# PCB_RTM_SATA.net
KiCad netlist of a schematic drawn in Altium Designer
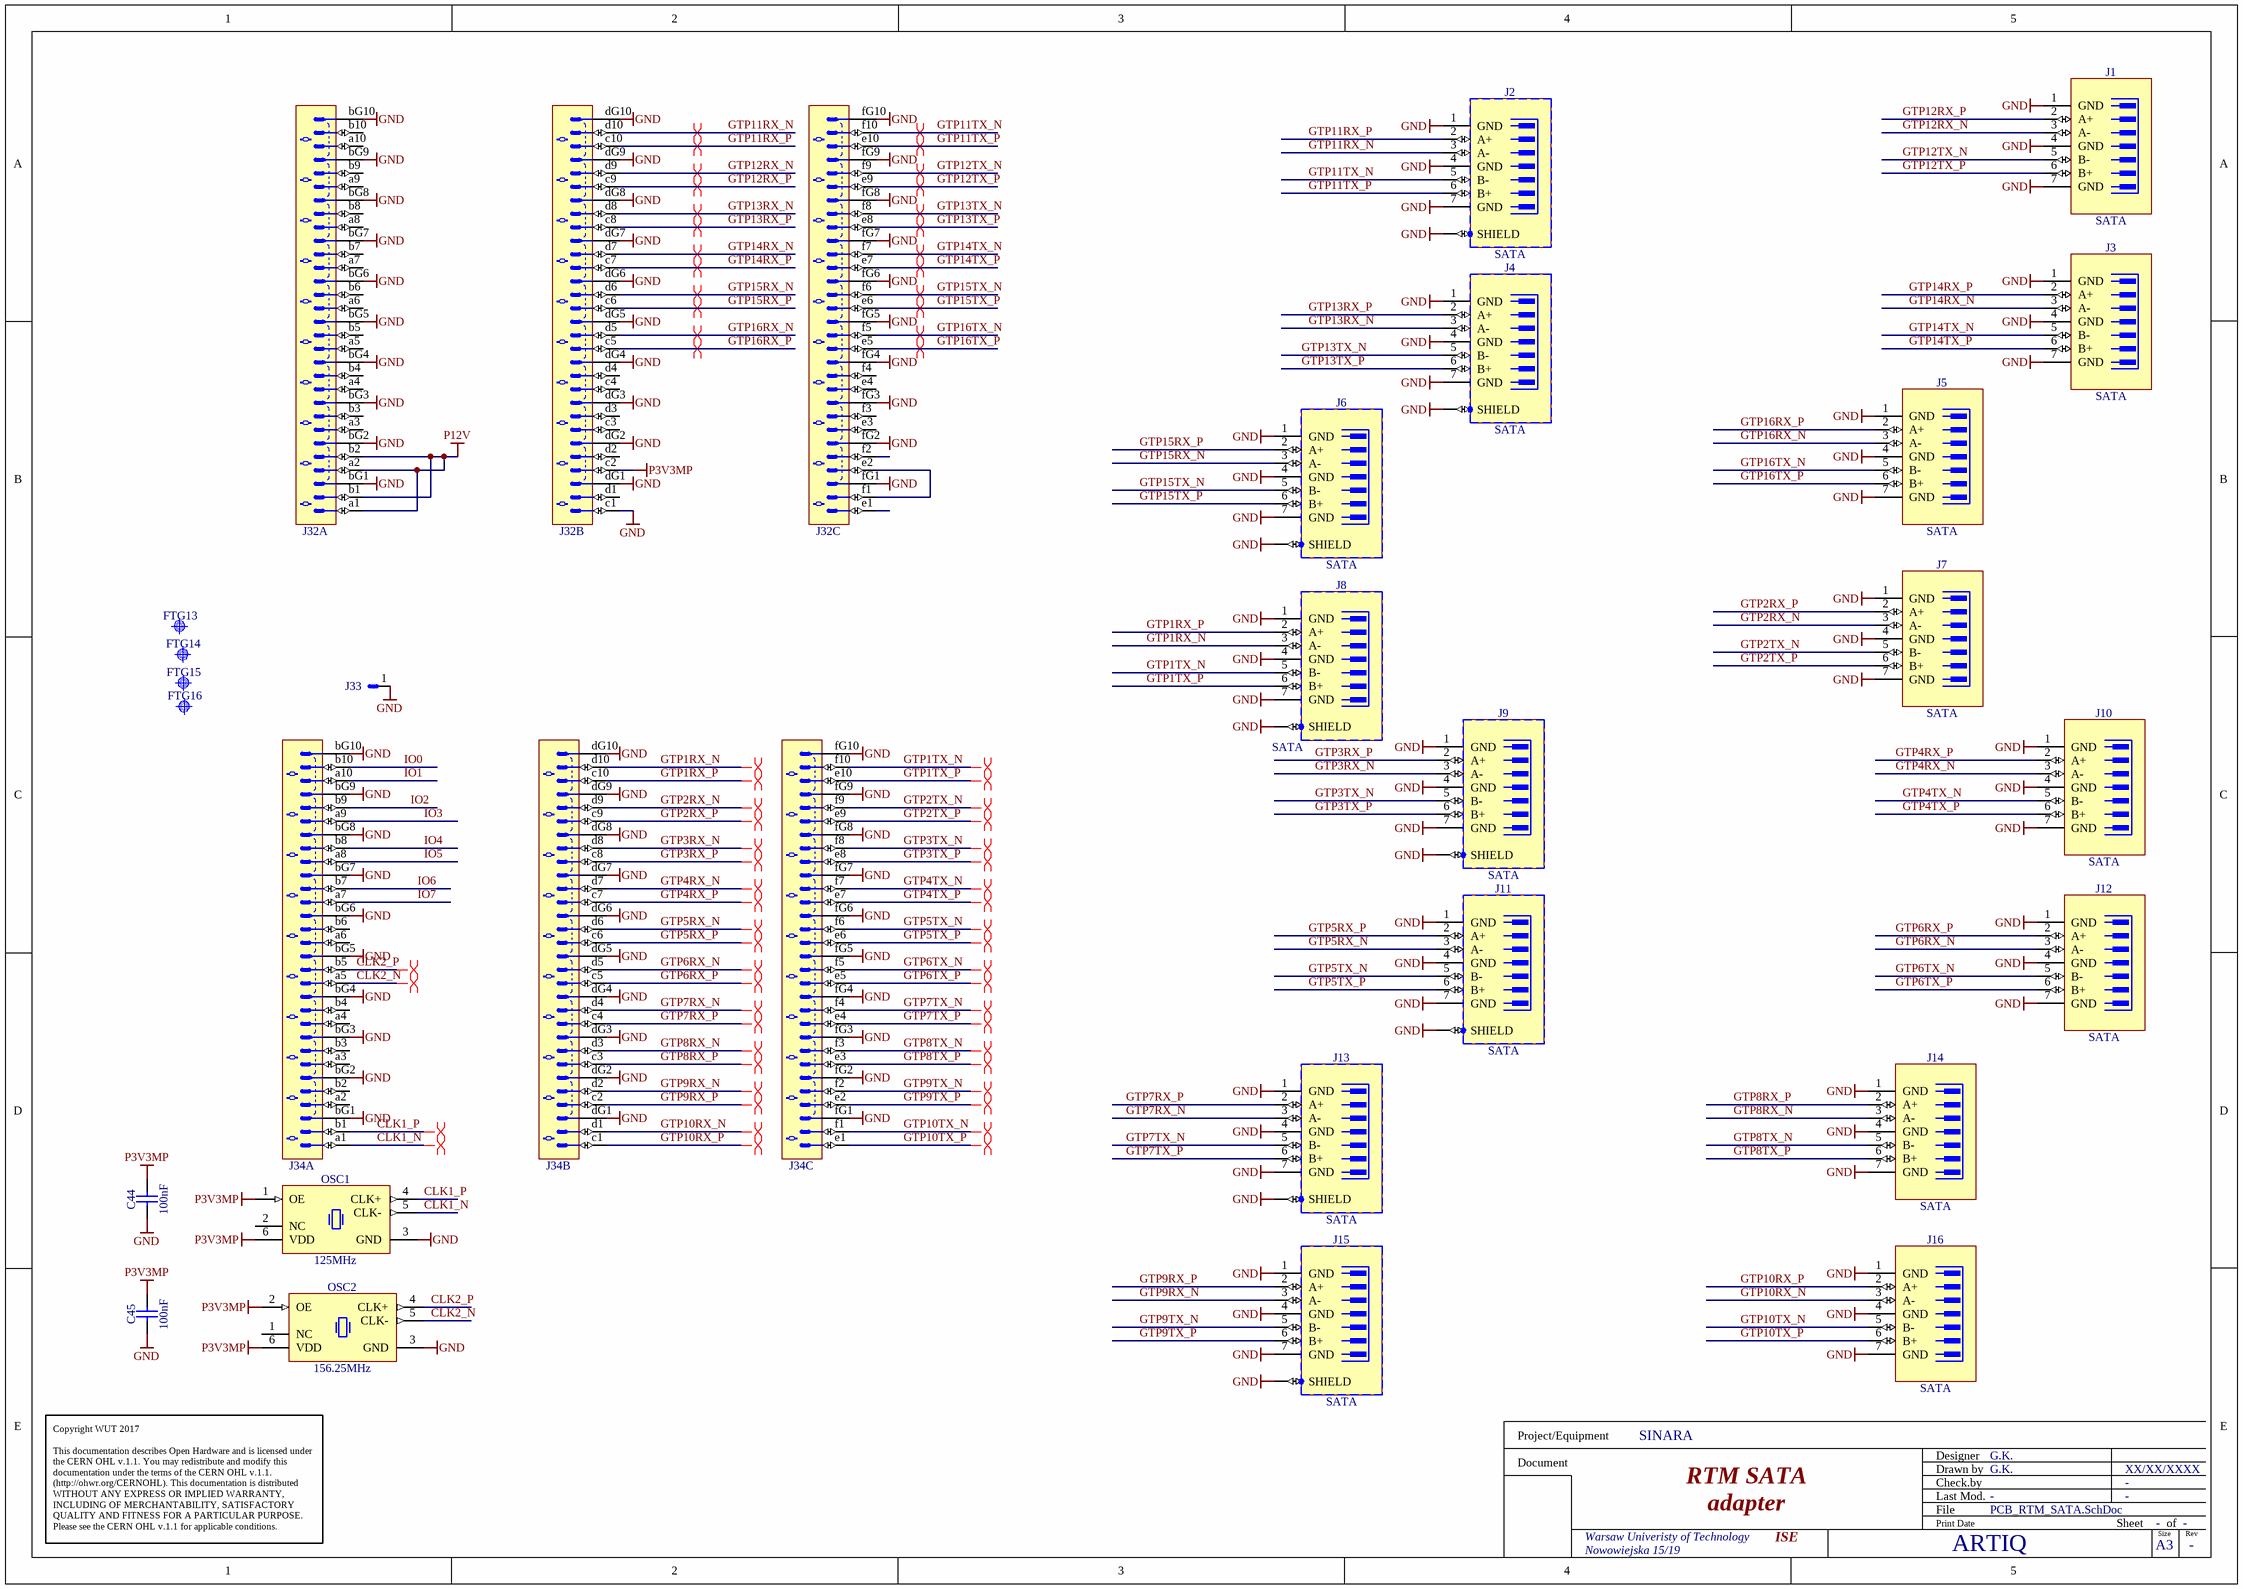
[diagram p0: PCB_RTM_SATA.SchDoc]

(export (version "E")
  (design (tool "Eeschema 10.0.6"))
  (components
    (comp (ref "C44")
      (value "100nF")
      (footprint "CAPC1005X55N")
      (description "Non-polarised capacitor")
      (fields
        (field (name "PART NUMBER") "CC0402_100NF_16V_10%_X7R")
        (field (name "VOLTAGE") "16V")
        (field (name "AUTHOR") "CERN DEM JLC")
      )
      (libsource (lib "Capacitors") (part "Capacitor - non polarized"))
    )
    (comp (ref "C45")
      (value "100nF")
      (footprint "CAPC1005X55N")
      (description "Non-polarised capacitor")
      (fields
        (field (name "PART NUMBER") "CC0402_100NF_16V_10%_X7R")
        (field (name "VOLTAGE") "16V")
        (field (name "AUTHOR") "CERN DEM JLC")
      )
      (libsource (lib "Capacitors") (part "Capacitor - non polarized"))
    )
    (comp (ref "FTG13")
      (value "Use only in PCB")
      (footprint "FIDUCIAL_TOP_C100-200")
      (description "Fiducial Target")
      (fields (field (name "PART NUMBER") "FIDUCIAL_TARGET_C100-200") (field (name "AUTHOR") "CERN DEM JLC"))
      (libsource (lib "Eletro-mechanical") (part "Fiducial Target"))
    )
    (comp (ref "FTG14")
      (value "Use only in PCB")
      (footprint "FIDUCIAL_TOP_S100-200")
      (description "Fiducial Target")
      (fields (field (name "PART NUMBER") "FIDUCIAL_TARGET_S100-200") (field (name "AUTHOR") "CERN DEM JLC"))
      (libsource (lib "Eletro-mechanical") (part "Fiducial Target"))
    )
    (comp (ref "FTG15")
      (value "Use only in PCB")
      (footprint "FIDUCIAL_TOP_S200-400")
      (description "Fiducial Target")
      (fields (field (name "PART NUMBER") "FIDUCIAL_TARGET_S200-400") (field (name "AUTHOR") "CERN DEM JLC"))
      (libsource (lib "Eletro-mechanical") (part "Fiducial Target"))
    )
    (comp (ref "FTG16")
      (value "Use only in PCB")
      (footprint "FIDUCIAL_TOP_S100-200")
      (description "Fiducial Target")
      (fields (field (name "PART NUMBER") "FIDUCIAL_TARGET_S100-200") (field (name "AUTHOR") "CERN DEM JLC"))
      (libsource (lib "Eletro-mechanical") (part "Fiducial Target"))
    )
    (comp (ref "J1")
      (value "SATA")
      (footprint "MOLEX_67800-5005")
      (description "7 Pin SATA Receptacle")
      (fields
        (field (name "PART NUMBER") "MOLEX_67800-5005")
        (field (name "MANUFACTURER") "MOLEX")
        (field (name "AUTHOR") "CERN DEM MR")
      )
      (libsource (lib "Connectors") (part "Connector SATA 7 Male"))
    )
    (comp (ref "J2")
      (value "SATA")
      (footprint "3M_5607-4200-SH")
      (description "7 Pin + 1 Shield SATA Receptacle")
      (fields
        (field (name "PART NUMBER") "3M_5607-4200-SH")
        (field (name "MANUFACTURER") "3M")
        (field (name "AUTHOR") "CERN DEM JLC")
      )
      (libsource (lib "Connectors") (part "Connector SATA 7 Male + 1 Shield"))
    )
    (comp (ref "J3")
      (value "SATA")
      (footprint "MOLEX_67800-5005")
      (description "7 Pin SATA Receptacle")
      (fields
        (field (name "PART NUMBER") "MOLEX_67800-5005")
        (field (name "MANUFACTURER") "MOLEX")
        (field (name "AUTHOR") "CERN DEM MR")
      )
      (libsource (lib "Connectors") (part "Connector SATA 7 Male"))
    )
    (comp (ref "J4")
      (value "SATA")
      (footprint "3M_5607-4200-SH")
      (description "7 Pin + 1 Shield SATA Receptacle")
      (fields
        (field (name "PART NUMBER") "3M_5607-4200-SH")
        (field (name "MANUFACTURER") "3M")
        (field (name "AUTHOR") "CERN DEM JLC")
      )
      (libsource (lib "Connectors") (part "Connector SATA 7 Male + 1 Shield"))
    )
    (comp (ref "J5")
      (value "SATA")
      (footprint "MOLEX_67800-5005")
      (description "7 Pin SATA Receptacle")
      (fields
        (field (name "PART NUMBER") "MOLEX_67800-5005")
        (field (name "MANUFACTURER") "MOLEX")
        (field (name "AUTHOR") "CERN DEM MR")
      )
      (libsource (lib "Connectors") (part "Connector SATA 7 Male"))
    )
    (comp (ref "J6")
      (value "SATA")
      (footprint "3M_5607-4200-SH")
      (description "7 Pin + 1 Shield SATA Receptacle")
      (fields
        (field (name "PART NUMBER") "3M_5607-4200-SH")
        (field (name "MANUFACTURER") "3M")
        (field (name "AUTHOR") "CERN DEM JLC")
      )
      (libsource (lib "Connectors") (part "Connector SATA 7 Male + 1 Shield"))
    )
    (comp (ref "J7")
      (value "SATA")
      (footprint "MOLEX_67800-5005")
      (description "7 Pin SATA Receptacle")
      (fields
        (field (name "PART NUMBER") "MOLEX_67800-5005")
        (field (name "MANUFACTURER") "MOLEX")
        (field (name "AUTHOR") "CERN DEM MR")
      )
      (libsource (lib "Connectors") (part "Connector SATA 7 Male"))
    )
    (comp (ref "J8")
      (value "SATA")
      (footprint "3M_5607-4200-SH")
      (description "7 Pin + 1 Shield SATA Receptacle")
      (fields
        (field (name "PART NUMBER") "3M_5607-4200-SH")
        (field (name "MANUFACTURER") "3M")
        (field (name "AUTHOR") "CERN DEM JLC")
      )
      (libsource (lib "Connectors") (part "Connector SATA 7 Male + 1 Shield"))
    )
    (comp (ref "J9")
      (value "SATA")
      (footprint "3M_5607-4200-SH")
      (description "7 Pin + 1 Shield SATA Receptacle")
      (fields
        (field (name "PART NUMBER") "3M_5607-4200-SH")
        (field (name "MANUFACTURER") "3M")
        (field (name "AUTHOR") "CERN DEM JLC")
      )
      (libsource (lib "Connectors") (part "Connector SATA 7 Male + 1 Shield"))
    )
    (comp (ref "J10")
      (value "SATA")
      (footprint "MOLEX_67800-5005")
      (description "7 Pin SATA Receptacle")
      (fields
        (field (name "PART NUMBER") "MOLEX_67800-5005")
        (field (name "MANUFACTURER") "MOLEX")
        (field (name "AUTHOR") "CERN DEM MR")
      )
      (libsource (lib "Connectors") (part "Connector SATA 7 Male"))
    )
    (comp (ref "J11")
      (value "SATA")
      (footprint "3M_5607-4200-SH")
      (description "7 Pin + 1 Shield SATA Receptacle")
      (fields
        (field (name "PART NUMBER") "3M_5607-4200-SH")
        (field (name "MANUFACTURER") "3M")
        (field (name "AUTHOR") "CERN DEM JLC")
      )
      (libsource (lib "Connectors") (part "Connector SATA 7 Male + 1 Shield"))
    )
    (comp (ref "J12")
      (value "SATA")
      (footprint "MOLEX_67800-5005")
      (description "7 Pin SATA Receptacle")
      (fields
        (field (name "PART NUMBER") "MOLEX_67800-5005")
        (field (name "MANUFACTURER") "MOLEX")
        (field (name "AUTHOR") "CERN DEM MR")
      )
      (libsource (lib "Connectors") (part "Connector SATA 7 Male"))
    )
    (comp (ref "J13")
      (value "SATA")
      (footprint "3M_5607-4200-SH")
      (description "7 Pin + 1 Shield SATA Receptacle")
      (fields
        (field (name "PART NUMBER") "3M_5607-4200-SH")
        (field (name "MANUFACTURER") "3M")
        (field (name "AUTHOR") "CERN DEM JLC")
      )
      (libsource (lib "Connectors") (part "Connector SATA 7 Male + 1 Shield"))
    )
    (comp (ref "J14")
      (value "SATA")
      (footprint "MOLEX_67800-5005")
      (description "7 Pin SATA Receptacle")
      (fields
        (field (name "PART NUMBER") "MOLEX_67800-5005")
        (field (name "MANUFACTURER") "MOLEX")
        (field (name "AUTHOR") "CERN DEM MR")
      )
      (libsource (lib "Connectors") (part "Connector SATA 7 Male"))
    )
    (comp (ref "J15")
      (value "SATA")
      (footprint "3M_5607-4200-SH")
      (description "7 Pin + 1 Shield SATA Receptacle")
      (fields
        (field (name "PART NUMBER") "3M_5607-4200-SH")
        (field (name "MANUFACTURER") "3M")
        (field (name "AUTHOR") "CERN DEM JLC")
      )
      (libsource (lib "Connectors") (part "Connector SATA 7 Male + 1 Shield"))
    )
    (comp (ref "J16")
      (value "SATA")
      (footprint "MOLEX_67800-5005")
      (description "7 Pin SATA Receptacle")
      (fields
        (field (name "PART NUMBER") "MOLEX_67800-5005")
        (field (name "MANUFACTURER") "MOLEX")
        (field (name "AUTHOR") "CERN DEM MR")
      )
      (libsource (lib "Connectors") (part "Connector SATA 7 Male"))
    )
    (comp (ref "J32")
      (value "~")
      (footprint "TYCO_6469183-1")
      (description "Connector 60 ATCA Male 30 Pairs (60 Signals) + 3x10 Ground")
      (fields (field (name "PART NUMBER") "TYCO_6469183-1"))
      (libsource (lib "Connectors") (part "Connector ATCA 60+30 Male"))
    )
    (comp (ref "J33")
      (value "~")
      (footprint "TYCO_1469265-1")
      (description "Single Pin Male")
      (fields (field (name "PART NUMBER") "TYCO_1469265-1"))
      (libsource (lib "Connectors") (part "Single Pin Male"))
    )
    (comp (ref "J34")
      (value "~")
      (footprint "TYCO_6469183-1")
      (description "Connector 60 ATCA Male 30 Pairs (60 Signals) + 3x10 Ground")
      (fields (field (name "PART NUMBER") "TYCO_6469183-1"))
      (libsource (lib "Connectors") (part "Connector ATCA 60+30 Male"))
    )
    (comp (ref "OSC1")
      (value "125MHz")
      (footprint "OSC_SILICON-LAB_SI531")
      (description "10-1400MHz, Crystal Oscillator (XO), Si531 Series")
      (fields
        (field (name "PART NUMBER") "OSC_125MHZ_SILICON-LAB_531BC125M000DG")
        (field (name "MANUFACTURER") "SILICON LABS")
        (field (name "AUTHOR") "CERN DEM MR")
      )
      (libsource (lib "ICs And Semiconductors") (part "Oscillator SILICON-LAB_Si531"))
    )
    (comp (ref "OSC2")
      (value "156.25MHz")
      (footprint "OSC_SILICON-LAB_SI530")
      (description "10-1400MHz, Crystal Oscillator (XO), Si530 Series")
      (fields
        (field (name "PART NUMBER") "OSC_156.25MHZ_SILICON-LAB_530BC156M250DG")
        (field (name "MANUFACTURER") "SILICON LABS")
        (field (name "AUTHOR") "CERN DEM MR")
      )
      (libsource (lib "ICs And Semiconductors") (part "Oscillator SILICON-LAB_Si530_a"))
    )
  )
  (nets
    (net (code "1") (name "/CLK1_N") (class "Default")
      (node (ref "J34") (pin "a1") (pinfunction "a1_a1") (pintype "bidirectional"))
      (node (ref "OSC1") (pin "5") (pinfunction "CLK-_5") (pintype "output"))
    )
    (net (code "2") (name "/CLK1_P") (class "Default")
      (node (ref "J34") (pin "b1") (pinfunction "b1_b1") (pintype "bidirectional"))
      (node (ref "OSC1") (pin "4") (pinfunction "CLK+_4") (pintype "output"))
    )
    (net (code "3") (name "/CLK2_N") (class "Default")
      (node (ref "J34") (pin "a5") (pinfunction "a5_a5") (pintype "bidirectional"))
      (node (ref "OSC2") (pin "5") (pinfunction "CLK-_5") (pintype "output"))
    )
    (net (code "4") (name "/CLK2_P") (class "Default")
      (node (ref "J34") (pin "b5") (pinfunction "b5_b5") (pintype "bidirectional"))
      (node (ref "OSC2") (pin "4") (pinfunction "CLK+_4") (pintype "output"))
    )
    (net (code "5") (name "/GTP1RX_N") (class "Default")
      (node (ref "J34") (pin "d10") (pinfunction "d10_d10") (pintype "bidirectional"))
      (node (ref "J8") (pin "3") (pinfunction "A-_3") (pintype "bidirectional"))
    )
    (net (code "6") (name "/GTP1RX_P") (class "Default")
      (node (ref "J34") (pin "c10") (pinfunction "c10_c10") (pintype "bidirectional"))
      (node (ref "J8") (pin "2") (pinfunction "A+_2") (pintype "bidirectional"))
    )
    (net (code "7") (name "/GTP1TX_N") (class "Default")
      (node (ref "J34") (pin "f10") (pinfunction "f10_f10") (pintype "bidirectional"))
      (node (ref "J8") (pin "5") (pinfunction "B-_5") (pintype "bidirectional"))
    )
    (net (code "8") (name "/GTP1TX_P") (class "Default")
      (node (ref "J34") (pin "e10") (pinfunction "e10_e10") (pintype "bidirectional"))
      (node (ref "J8") (pin "6") (pinfunction "B+_6") (pintype "bidirectional"))
    )
    (net (code "9") (name "/GTP2RX_N") (class "Default")
      (node (ref "J34") (pin "d9") (pinfunction "d9_d9") (pintype "bidirectional"))
      (node (ref "J7") (pin "3") (pinfunction "A-_3") (pintype "bidirectional"))
    )
    (net (code "10") (name "/GTP2RX_P") (class "Default")
      (node (ref "J34") (pin "c9") (pinfunction "c9_c9") (pintype "bidirectional"))
      (node (ref "J7") (pin "2") (pinfunction "A+_2") (pintype "bidirectional"))
    )
    (net (code "11") (name "/GTP2TX_N") (class "Default")
      (node (ref "J34") (pin "f9") (pinfunction "f9_f9") (pintype "bidirectional"))
      (node (ref "J7") (pin "5") (pinfunction "B-_5") (pintype "bidirectional"))
    )
    (net (code "12") (name "/GTP2TX_P") (class "Default")
      (node (ref "J34") (pin "e9") (pinfunction "e9_e9") (pintype "bidirectional"))
      (node (ref "J7") (pin "6") (pinfunction "B+_6") (pintype "bidirectional"))
    )
    (net (code "13") (name "/GTP3RX_N") (class "Default")
      (node (ref "J34") (pin "d8") (pinfunction "d8_d8") (pintype "bidirectional"))
      (node (ref "J9") (pin "3") (pinfunction "A-_3") (pintype "bidirectional"))
    )
    (net (code "14") (name "/GTP3RX_P") (class "Default")
      (node (ref "J34") (pin "c8") (pinfunction "c8_c8") (pintype "bidirectional"))
      (node (ref "J9") (pin "2") (pinfunction "A+_2") (pintype "bidirectional"))
    )
    (net (code "15") (name "/GTP3TX_N") (class "Default")
      (node (ref "J34") (pin "f8") (pinfunction "f8_f8") (pintype "bidirectional"))
      (node (ref "J9") (pin "5") (pinfunction "B-_5") (pintype "bidirectional"))
    )
    (net (code "16") (name "/GTP3TX_P") (class "Default")
      (node (ref "J34") (pin "e8") (pinfunction "e8_e8") (pintype "bidirectional"))
      (node (ref "J9") (pin "6") (pinfunction "B+_6") (pintype "bidirectional"))
    )
    (net (code "17") (name "/GTP4RX_N") (class "Default")
      (node (ref "J10") (pin "3") (pinfunction "A-_3") (pintype "bidirectional"))
      (node (ref "J34") (pin "d7") (pinfunction "d7_d7") (pintype "bidirectional"))
    )
    (net (code "18") (name "/GTP4RX_P") (class "Default")
      (node (ref "J10") (pin "2") (pinfunction "A+_2") (pintype "bidirectional"))
      (node (ref "J34") (pin "c7") (pinfunction "c7_c7") (pintype "bidirectional"))
    )
    (net (code "19") (name "/GTP4TX_N") (class "Default")
      (node (ref "J10") (pin "5") (pinfunction "B-_5") (pintype "bidirectional"))
      (node (ref "J34") (pin "f7") (pinfunction "f7_f7") (pintype "bidirectional"))
    )
    (net (code "20") (name "/GTP4TX_P") (class "Default")
      (node (ref "J10") (pin "6") (pinfunction "B+_6") (pintype "bidirectional"))
      (node (ref "J34") (pin "e7") (pinfunction "e7_e7") (pintype "bidirectional"))
    )
    (net (code "21") (name "/GTP5RX_N") (class "Default")
      (node (ref "J11") (pin "3") (pinfunction "A-_3") (pintype "bidirectional"))
      (node (ref "J34") (pin "d6") (pinfunction "d6_d6") (pintype "bidirectional"))
    )
    (net (code "22") (name "/GTP5RX_P") (class "Default")
      (node (ref "J11") (pin "2") (pinfunction "A+_2") (pintype "bidirectional"))
      (node (ref "J34") (pin "c6") (pinfunction "c6_c6") (pintype "bidirectional"))
    )
    (net (code "23") (name "/GTP5TX_N") (class "Default")
      (node (ref "J11") (pin "5") (pinfunction "B-_5") (pintype "bidirectional"))
      (node (ref "J34") (pin "f6") (pinfunction "f6_f6") (pintype "bidirectional"))
    )
    (net (code "24") (name "/GTP5TX_P") (class "Default")
      (node (ref "J11") (pin "6") (pinfunction "B+_6") (pintype "bidirectional"))
      (node (ref "J34") (pin "e6") (pinfunction "e6_e6") (pintype "bidirectional"))
    )
    (net (code "25") (name "/GTP6RX_N") (class "Default")
      (node (ref "J12") (pin "3") (pinfunction "A-_3") (pintype "bidirectional"))
      (node (ref "J34") (pin "d5") (pinfunction "d5_d5") (pintype "bidirectional"))
    )
    (net (code "26") (name "/GTP6RX_P") (class "Default")
      (node (ref "J12") (pin "2") (pinfunction "A+_2") (pintype "bidirectional"))
      (node (ref "J34") (pin "c5") (pinfunction "c5_c5") (pintype "bidirectional"))
    )
    (net (code "27") (name "/GTP6TX_N") (class "Default")
      (node (ref "J12") (pin "5") (pinfunction "B-_5") (pintype "bidirectional"))
      (node (ref "J34") (pin "f5") (pinfunction "f5_f5") (pintype "bidirectional"))
    )
    (net (code "28") (name "/GTP6TX_P") (class "Default")
      (node (ref "J12") (pin "6") (pinfunction "B+_6") (pintype "bidirectional"))
      (node (ref "J34") (pin "e5") (pinfunction "e5_e5") (pintype "bidirectional"))
    )
    (net (code "29") (name "/GTP7RX_N") (class "Default")
      (node (ref "J13") (pin "3") (pinfunction "A-_3") (pintype "bidirectional"))
      (node (ref "J34") (pin "d4") (pinfunction "d4_d4") (pintype "bidirectional"))
    )
    (net (code "30") (name "/GTP7RX_P") (class "Default")
      (node (ref "J13") (pin "2") (pinfunction "A+_2") (pintype "bidirectional"))
      (node (ref "J34") (pin "c4") (pinfunction "c4_c4") (pintype "bidirectional"))
    )
    (net (code "31") (name "/GTP7TX_N") (class "Default")
      (node (ref "J13") (pin "5") (pinfunction "B-_5") (pintype "bidirectional"))
      (node (ref "J34") (pin "f4") (pinfunction "f4_f4") (pintype "bidirectional"))
    )
    (net (code "32") (name "/GTP7TX_P") (class "Default")
      (node (ref "J13") (pin "6") (pinfunction "B+_6") (pintype "bidirectional"))
      (node (ref "J34") (pin "e4") (pinfunction "e4_e4") (pintype "bidirectional"))
    )
    (net (code "33") (name "/GTP8RX_N") (class "Default")
      (node (ref "J14") (pin "3") (pinfunction "A-_3") (pintype "bidirectional"))
      (node (ref "J34") (pin "d3") (pinfunction "d3_d3") (pintype "bidirectional"))
    )
    (net (code "34") (name "/GTP8RX_P") (class "Default")
      (node (ref "J14") (pin "2") (pinfunction "A+_2") (pintype "bidirectional"))
      (node (ref "J34") (pin "c3") (pinfunction "c3_c3") (pintype "bidirectional"))
    )
    (net (code "35") (name "/GTP8TX_N") (class "Default")
      (node (ref "J14") (pin "5") (pinfunction "B-_5") (pintype "bidirectional"))
      (node (ref "J34") (pin "f3") (pinfunction "f3_f3") (pintype "bidirectional"))
    )
    (net (code "36") (name "/GTP8TX_P") (class "Default")
      (node (ref "J14") (pin "6") (pinfunction "B+_6") (pintype "bidirectional"))
      (node (ref "J34") (pin "e3") (pinfunction "e3_e3") (pintype "bidirectional"))
    )
    (net (code "37") (name "/GTP9RX_N") (class "Default")
      (node (ref "J15") (pin "3") (pinfunction "A-_3") (pintype "bidirectional"))
      (node (ref "J34") (pin "d2") (pinfunction "d2_d2") (pintype "bidirectional"))
    )
    (net (code "38") (name "/GTP9RX_P") (class "Default")
      (node (ref "J15") (pin "2") (pinfunction "A+_2") (pintype "bidirectional"))
      (node (ref "J34") (pin "c2") (pinfunction "c2_c2") (pintype "bidirectional"))
    )
    (net (code "39") (name "/GTP9TX_N") (class "Default")
      (node (ref "J15") (pin "5") (pinfunction "B-_5") (pintype "bidirectional"))
      (node (ref "J34") (pin "f2") (pinfunction "f2_f2") (pintype "bidirectional"))
    )
    (net (code "40") (name "/GTP9TX_P") (class "Default")
      (node (ref "J15") (pin "6") (pinfunction "B+_6") (pintype "bidirectional"))
      (node (ref "J34") (pin "e2") (pinfunction "e2_e2") (pintype "bidirectional"))
    )
    (net (code "41") (name "/GTP10RX_N") (class "Default")
      (node (ref "J16") (pin "3") (pinfunction "A-_3") (pintype "bidirectional"))
      (node (ref "J34") (pin "d1") (pinfunction "d1_d1") (pintype "bidirectional"))
    )
    (net (code "42") (name "/GTP10RX_P") (class "Default")
      (node (ref "J16") (pin "2") (pinfunction "A+_2") (pintype "bidirectional"))
      (node (ref "J34") (pin "c1") (pinfunction "c1_c1") (pintype "bidirectional"))
    )
    (net (code "43") (name "/GTP10TX_N") (class "Default")
      (node (ref "J16") (pin "5") (pinfunction "B-_5") (pintype "bidirectional"))
      (node (ref "J34") (pin "f1") (pinfunction "f1_f1") (pintype "bidirectional"))
    )
    (net (code "44") (name "/GTP10TX_P") (class "Default")
      (node (ref "J16") (pin "6") (pinfunction "B+_6") (pintype "bidirectional"))
      (node (ref "J34") (pin "e1") (pinfunction "e1_e1") (pintype "bidirectional"))
    )
    (net (code "45") (name "/GTP11RX_N") (class "Default")
      (node (ref "J2") (pin "3") (pinfunction "A-_3") (pintype "bidirectional"))
      (node (ref "J32") (pin "d10") (pinfunction "d10_d10") (pintype "bidirectional"))
    )
    (net (code "46") (name "/GTP11RX_P") (class "Default")
      (node (ref "J2") (pin "2") (pinfunction "A+_2") (pintype "bidirectional"))
      (node (ref "J32") (pin "c10") (pinfunction "c10_c10") (pintype "bidirectional"))
    )
    (net (code "47") (name "/GTP11TX_N") (class "Default")
      (node (ref "J2") (pin "5") (pinfunction "B-_5") (pintype "bidirectional"))
      (node (ref "J32") (pin "f10") (pinfunction "f10_f10") (pintype "bidirectional"))
    )
    (net (code "48") (name "/GTP11TX_P") (class "Default")
      (node (ref "J2") (pin "6") (pinfunction "B+_6") (pintype "bidirectional"))
      (node (ref "J32") (pin "e10") (pinfunction "e10_e10") (pintype "bidirectional"))
    )
    (net (code "49") (name "/GTP12RX_N") (class "Default")
      (node (ref "J1") (pin "3") (pinfunction "A-_3") (pintype "bidirectional"))
      (node (ref "J32") (pin "d9") (pinfunction "d9_d9") (pintype "bidirectional"))
    )
    (net (code "50") (name "/GTP12RX_P") (class "Default")
      (node (ref "J1") (pin "2") (pinfunction "A+_2") (pintype "bidirectional"))
      (node (ref "J32") (pin "c9") (pinfunction "c9_c9") (pintype "bidirectional"))
    )
    (net (code "51") (name "/GTP12TX_N") (class "Default")
      (node (ref "J1") (pin "5") (pinfunction "B-_5") (pintype "bidirectional"))
      (node (ref "J32") (pin "f9") (pinfunction "f9_f9") (pintype "bidirectional"))
    )
    (net (code "52") (name "/GTP12TX_P") (class "Default")
      (node (ref "J1") (pin "6") (pinfunction "B+_6") (pintype "bidirectional"))
      (node (ref "J32") (pin "e9") (pinfunction "e9_e9") (pintype "bidirectional"))
    )
    (net (code "53") (name "/GTP13RX_N") (class "Default")
      (node (ref "J32") (pin "d8") (pinfunction "d8_d8") (pintype "bidirectional"))
      (node (ref "J4") (pin "3") (pinfunction "A-_3") (pintype "bidirectional"))
    )
    (net (code "54") (name "/GTP13RX_P") (class "Default")
      (node (ref "J32") (pin "c8") (pinfunction "c8_c8") (pintype "bidirectional"))
      (node (ref "J4") (pin "2") (pinfunction "A+_2") (pintype "bidirectional"))
    )
    (net (code "55") (name "/GTP13TX_N") (class "Default")
      (node (ref "J32") (pin "f8") (pinfunction "f8_f8") (pintype "bidirectional"))
      (node (ref "J4") (pin "5") (pinfunction "B-_5") (pintype "bidirectional"))
    )
    (net (code "56") (name "/GTP13TX_P") (class "Default")
      (node (ref "J32") (pin "e8") (pinfunction "e8_e8") (pintype "bidirectional"))
      (node (ref "J4") (pin "6") (pinfunction "B+_6") (pintype "bidirectional"))
    )
    (net (code "57") (name "/GTP14RX_N") (class "Default")
      (node (ref "J3") (pin "3") (pinfunction "A-_3") (pintype "bidirectional"))
      (node (ref "J32") (pin "d7") (pinfunction "d7_d7") (pintype "bidirectional"))
    )
    (net (code "58") (name "/GTP14RX_P") (class "Default")
      (node (ref "J3") (pin "2") (pinfunction "A+_2") (pintype "bidirectional"))
      (node (ref "J32") (pin "c7") (pinfunction "c7_c7") (pintype "bidirectional"))
    )
    (net (code "59") (name "/GTP14TX_N") (class "Default")
      (node (ref "J3") (pin "5") (pinfunction "B-_5") (pintype "bidirectional"))
      (node (ref "J32") (pin "f7") (pinfunction "f7_f7") (pintype "bidirectional"))
    )
    (net (code "60") (name "/GTP14TX_P") (class "Default")
      (node (ref "J3") (pin "6") (pinfunction "B+_6") (pintype "bidirectional"))
      (node (ref "J32") (pin "e7") (pinfunction "e7_e7") (pintype "bidirectional"))
    )
    (net (code "61") (name "/GTP15RX_N") (class "Default")
      (node (ref "J32") (pin "d6") (pinfunction "d6_d6") (pintype "bidirectional"))
      (node (ref "J6") (pin "3") (pinfunction "A-_3") (pintype "bidirectional"))
    )
    (net (code "62") (name "/GTP15RX_P") (class "Default")
      (node (ref "J32") (pin "c6") (pinfunction "c6_c6") (pintype "bidirectional"))
      (node (ref "J6") (pin "2") (pinfunction "A+_2") (pintype "bidirectional"))
    )
    (net (code "63") (name "/GTP15TX_N") (class "Default")
      (node (ref "J32") (pin "f6") (pinfunction "f6_f6") (pintype "bidirectional"))
      (node (ref "J6") (pin "5") (pinfunction "B-_5") (pintype "bidirectional"))
    )
    (net (code "64") (name "/GTP15TX_P") (class "Default")
      (node (ref "J32") (pin "e6") (pinfunction "e6_e6") (pintype "bidirectional"))
      (node (ref "J6") (pin "6") (pinfunction "B+_6") (pintype "bidirectional"))
    )
    (net (code "65") (name "/GTP16RX_N") (class "Default")
      (node (ref "J32") (pin "d5") (pinfunction "d5_d5") (pintype "bidirectional"))
      (node (ref "J5") (pin "3") (pinfunction "A-_3") (pintype "bidirectional"))
    )
    (net (code "66") (name "/GTP16RX_P") (class "Default")
      (node (ref "J32") (pin "c5") (pinfunction "c5_c5") (pintype "bidirectional"))
      (node (ref "J5") (pin "2") (pinfunction "A+_2") (pintype "bidirectional"))
    )
    (net (code "67") (name "/GTP16TX_N") (class "Default")
      (node (ref "J32") (pin "f5") (pinfunction "f5_f5") (pintype "bidirectional"))
      (node (ref "J5") (pin "5") (pinfunction "B-_5") (pintype "bidirectional"))
    )
    (net (code "68") (name "/GTP16TX_P") (class "Default")
      (node (ref "J32") (pin "e5") (pinfunction "e5_e5") (pintype "bidirectional"))
      (node (ref "J5") (pin "6") (pinfunction "B+_6") (pintype "bidirectional"))
    )
    (net (code "69") (name "/IO0") (class "Default")
      (node (ref "J34") (pin "b10") (pinfunction "b10_b10") (pintype "bidirectional"))
    )
    (net (code "70") (name "/IO1") (class "Default")
      (node (ref "J34") (pin "a10") (pinfunction "a10_a10") (pintype "bidirectional"))
    )
    (net (code "71") (name "/IO2") (class "Default")
      (node (ref "J34") (pin "b9") (pinfunction "b9_b9") (pintype "bidirectional"))
    )
    (net (code "72") (name "/IO3") (class "Default")
      (node (ref "J34") (pin "a9") (pinfunction "a9_a9") (pintype "bidirectional"))
    )
    (net (code "73") (name "/IO4") (class "Default")
      (node (ref "J34") (pin "b8") (pinfunction "b8_b8") (pintype "bidirectional"))
    )
    (net (code "74") (name "/IO5") (class "Default")
      (node (ref "J34") (pin "a8") (pinfunction "a8_a8") (pintype "bidirectional"))
    )
    (net (code "75") (name "/IO6") (class "Default")
      (node (ref "J34") (pin "b7") (pinfunction "b7_b7") (pintype "bidirectional"))
    )
    (net (code "76") (name "/IO7") (class "Default")
      (node (ref "J34") (pin "a7") (pinfunction "a7_a7") (pintype "bidirectional"))
    )
    (net (code "77") (name "GND") (class "Default")
      (node (ref "C44") (pin "1") (pinfunction "1_1") (pintype "passive"))
      (node (ref "C45") (pin "1") (pinfunction "1_1") (pintype "passive"))
      (node (ref "J1") (pin "1") (pinfunction "GND_1") (pintype "power_in"))
      (node (ref "J1") (pin "4") (pinfunction "GND_4") (pintype "power_in"))
      (node (ref "J1") (pin "7") (pinfunction "GND_7") (pintype "power_in"))
      (node (ref "J10") (pin "1") (pinfunction "GND_1") (pintype "power_in"))
      (node (ref "J10") (pin "4") (pinfunction "GND_4") (pintype "power_in"))
      (node (ref "J10") (pin "7") (pinfunction "GND_7") (pintype "power_in"))
      (node (ref "J11") (pin "1") (pinfunction "GND_1") (pintype "power_in"))
      (node (ref "J11") (pin "4") (pinfunction "GND_4") (pintype "power_in"))
      (node (ref "J11") (pin "7") (pinfunction "GND_7") (pintype "power_in"))
      (node (ref "J11") (pin "8") (pinfunction "SHIELD_8") (pintype "bidirectional"))
      (node (ref "J12") (pin "1") (pinfunction "GND_1") (pintype "power_in"))
      (node (ref "J12") (pin "4") (pinfunction "GND_4") (pintype "power_in"))
      (node (ref "J12") (pin "7") (pinfunction "GND_7") (pintype "power_in"))
      (node (ref "J13") (pin "1") (pinfunction "GND_1") (pintype "power_in"))
      (node (ref "J13") (pin "4") (pinfunction "GND_4") (pintype "power_in"))
      (node (ref "J13") (pin "7") (pinfunction "GND_7") (pintype "power_in"))
      (node (ref "J13") (pin "8") (pinfunction "SHIELD_8") (pintype "bidirectional"))
      (node (ref "J14") (pin "1") (pinfunction "GND_1") (pintype "power_in"))
      (node (ref "J14") (pin "4") (pinfunction "GND_4") (pintype "power_in"))
      (node (ref "J14") (pin "7") (pinfunction "GND_7") (pintype "power_in"))
      (node (ref "J15") (pin "1") (pinfunction "GND_1") (pintype "power_in"))
      (node (ref "J15") (pin "4") (pinfunction "GND_4") (pintype "power_in"))
      (node (ref "J15") (pin "7") (pinfunction "GND_7") (pintype "power_in"))
      (node (ref "J15") (pin "8") (pinfunction "SHIELD_8") (pintype "bidirectional"))
      (node (ref "J16") (pin "1") (pinfunction "GND_1") (pintype "power_in"))
      (node (ref "J16") (pin "4") (pinfunction "GND_4") (pintype "power_in"))
      (node (ref "J16") (pin "7") (pinfunction "GND_7") (pintype "power_in"))
      (node (ref "J2") (pin "1") (pinfunction "GND_1") (pintype "power_in"))
      (node (ref "J2") (pin "4") (pinfunction "GND_4") (pintype "power_in"))
      (node (ref "J2") (pin "7") (pinfunction "GND_7") (pintype "power_in"))
      (node (ref "J2") (pin "8") (pinfunction "SHIELD_8") (pintype "bidirectional"))
      (node (ref "J3") (pin "1") (pinfunction "GND_1") (pintype "power_in"))
      (node (ref "J3") (pin "4") (pinfunction "GND_4") (pintype "power_in"))
      (node (ref "J3") (pin "7") (pinfunction "GND_7") (pintype "power_in"))
      (node (ref "J32") (pin "bG1") (pinfunction "bG1_bG1") (pintype "power_in"))
      (node (ref "J32") (pin "bG10") (pinfunction "bG10_bG10") (pintype "power_in"))
      (node (ref "J32") (pin "bG2") (pinfunction "bG2_bG2") (pintype "power_in"))
      (node (ref "J32") (pin "bG3") (pinfunction "bG3_bG3") (pintype "power_in"))
      (node (ref "J32") (pin "bG4") (pinfunction "bG4_bG4") (pintype "power_in"))
      (node (ref "J32") (pin "bG5") (pinfunction "bG5_bG5") (pintype "power_in"))
      (node (ref "J32") (pin "bG6") (pinfunction "bG6_bG6") (pintype "power_in"))
      (node (ref "J32") (pin "bG7") (pinfunction "bG7_bG7") (pintype "power_in"))
      (node (ref "J32") (pin "bG8") (pinfunction "bG8_bG8") (pintype "power_in"))
      (node (ref "J32") (pin "bG9") (pinfunction "bG9_bG9") (pintype "power_in"))
      (node (ref "J32") (pin "c1") (pinfunction "c1_c1") (pintype "bidirectional"))
      (node (ref "J32") (pin "dG1") (pinfunction "dG1_dG1") (pintype "power_in"))
      (node (ref "J32") (pin "dG10") (pinfunction "dG10_dG10") (pintype "power_in"))
      (node (ref "J32") (pin "dG2") (pinfunction "dG2_dG2") (pintype "power_in"))
      (node (ref "J32") (pin "dG3") (pinfunction "dG3_dG3") (pintype "power_in"))
      (node (ref "J32") (pin "dG4") (pinfunction "dG4_dG4") (pintype "power_in"))
      (node (ref "J32") (pin "dG5") (pinfunction "dG5_dG5") (pintype "power_in"))
      (node (ref "J32") (pin "dG6") (pinfunction "dG6_dG6") (pintype "power_in"))
      (node (ref "J32") (pin "dG7") (pinfunction "dG7_dG7") (pintype "power_in"))
      (node (ref "J32") (pin "dG8") (pinfunction "dG8_dG8") (pintype "power_in"))
      (node (ref "J32") (pin "dG9") (pinfunction "dG9_dG9") (pintype "power_in"))
      (node (ref "J32") (pin "fG1") (pinfunction "fG1_fG1") (pintype "power_in"))
      (node (ref "J32") (pin "fG10") (pinfunction "fG10_fG10") (pintype "power_in"))
      (node (ref "J32") (pin "fG2") (pinfunction "fG2_fG2") (pintype "power_in"))
      (node (ref "J32") (pin "fG3") (pinfunction "fG3_fG3") (pintype "power_in"))
      (node (ref "J32") (pin "fG4") (pinfunction "fG4_fG4") (pintype "power_in"))
      (node (ref "J32") (pin "fG5") (pinfunction "fG5_fG5") (pintype "power_in"))
      (node (ref "J32") (pin "fG6") (pinfunction "fG6_fG6") (pintype "power_in"))
      (node (ref "J32") (pin "fG7") (pinfunction "fG7_fG7") (pintype "power_in"))
      (node (ref "J32") (pin "fG8") (pinfunction "fG8_fG8") (pintype "power_in"))
      (node (ref "J32") (pin "fG9") (pinfunction "fG9_fG9") (pintype "power_in"))
      (node (ref "J33") (pin "1") (pinfunction "1_1") (pintype "bidirectional"))
      (node (ref "J34") (pin "bG1") (pinfunction "bG1_bG1") (pintype "power_in"))
      (node (ref "J34") (pin "bG10") (pinfunction "bG10_bG10") (pintype "power_in"))
      (node (ref "J34") (pin "bG2") (pinfunction "bG2_bG2") (pintype "power_in"))
      (node (ref "J34") (pin "bG3") (pinfunction "bG3_bG3") (pintype "power_in"))
      (node (ref "J34") (pin "bG4") (pinfunction "bG4_bG4") (pintype "power_in"))
      (node (ref "J34") (pin "bG5") (pinfunction "bG5_bG5") (pintype "power_in"))
      (node (ref "J34") (pin "bG6") (pinfunction "bG6_bG6") (pintype "power_in"))
      (node (ref "J34") (pin "bG7") (pinfunction "bG7_bG7") (pintype "power_in"))
      (node (ref "J34") (pin "bG8") (pinfunction "bG8_bG8") (pintype "power_in"))
      (node (ref "J34") (pin "bG9") (pinfunction "bG9_bG9") (pintype "power_in"))
      (node (ref "J34") (pin "dG1") (pinfunction "dG1_dG1") (pintype "power_in"))
      (node (ref "J34") (pin "dG10") (pinfunction "dG10_dG10") (pintype "power_in"))
      (node (ref "J34") (pin "dG2") (pinfunction "dG2_dG2") (pintype "power_in"))
      (node (ref "J34") (pin "dG3") (pinfunction "dG3_dG3") (pintype "power_in"))
      (node (ref "J34") (pin "dG4") (pinfunction "dG4_dG4") (pintype "power_in"))
      (node (ref "J34") (pin "dG5") (pinfunction "dG5_dG5") (pintype "power_in"))
      (node (ref "J34") (pin "dG6") (pinfunction "dG6_dG6") (pintype "power_in"))
      (node (ref "J34") (pin "dG7") (pinfunction "dG7_dG7") (pintype "power_in"))
      (node (ref "J34") (pin "dG8") (pinfunction "dG8_dG8") (pintype "power_in"))
      (node (ref "J34") (pin "dG9") (pinfunction "dG9_dG9") (pintype "power_in"))
      (node (ref "J34") (pin "fG1") (pinfunction "fG1_fG1") (pintype "power_in"))
      (node (ref "J34") (pin "fG10") (pinfunction "fG10_fG10") (pintype "power_in"))
      (node (ref "J34") (pin "fG2") (pinfunction "fG2_fG2") (pintype "power_in"))
      (node (ref "J34") (pin "fG3") (pinfunction "fG3_fG3") (pintype "power_in"))
      (node (ref "J34") (pin "fG4") (pinfunction "fG4_fG4") (pintype "power_in"))
      (node (ref "J34") (pin "fG5") (pinfunction "fG5_fG5") (pintype "power_in"))
      (node (ref "J34") (pin "fG6") (pinfunction "fG6_fG6") (pintype "power_in"))
      (node (ref "J34") (pin "fG7") (pinfunction "fG7_fG7") (pintype "power_in"))
      (node (ref "J34") (pin "fG8") (pinfunction "fG8_fG8") (pintype "power_in"))
      (node (ref "J34") (pin "fG9") (pinfunction "fG9_fG9") (pintype "power_in"))
      (node (ref "J4") (pin "1") (pinfunction "GND_1") (pintype "power_in"))
      (node (ref "J4") (pin "4") (pinfunction "GND_4") (pintype "power_in"))
      (node (ref "J4") (pin "7") (pinfunction "GND_7") (pintype "power_in"))
      (node (ref "J4") (pin "8") (pinfunction "SHIELD_8") (pintype "bidirectional"))
      (node (ref "J5") (pin "1") (pinfunction "GND_1") (pintype "power_in"))
      (node (ref "J5") (pin "4") (pinfunction "GND_4") (pintype "power_in"))
      (node (ref "J5") (pin "7") (pinfunction "GND_7") (pintype "power_in"))
      (node (ref "J6") (pin "1") (pinfunction "GND_1") (pintype "power_in"))
      (node (ref "J6") (pin "4") (pinfunction "GND_4") (pintype "power_in"))
      (node (ref "J6") (pin "7") (pinfunction "GND_7") (pintype "power_in"))
      (node (ref "J6") (pin "8") (pinfunction "SHIELD_8") (pintype "bidirectional"))
      (node (ref "J7") (pin "1") (pinfunction "GND_1") (pintype "power_in"))
      (node (ref "J7") (pin "4") (pinfunction "GND_4") (pintype "power_in"))
      (node (ref "J7") (pin "7") (pinfunction "GND_7") (pintype "power_in"))
      (node (ref "J8") (pin "1") (pinfunction "GND_1") (pintype "power_in"))
      (node (ref "J8") (pin "4") (pinfunction "GND_4") (pintype "power_in"))
      (node (ref "J8") (pin "7") (pinfunction "GND_7") (pintype "power_in"))
      (node (ref "J8") (pin "8") (pinfunction "SHIELD_8") (pintype "bidirectional"))
      (node (ref "J9") (pin "1") (pinfunction "GND_1") (pintype "power_in"))
      (node (ref "J9") (pin "4") (pinfunction "GND_4") (pintype "power_in"))
      (node (ref "J9") (pin "7") (pinfunction "GND_7") (pintype "power_in"))
      (node (ref "J9") (pin "8") (pinfunction "SHIELD_8") (pintype "bidirectional"))
      (node (ref "OSC1") (pin "3") (pinfunction "GND_3") (pintype "power_in"))
      (node (ref "OSC2") (pin "3") (pinfunction "GND_3") (pintype "power_in"))
    )
    (net (code "78") (name "Net-(J32-Pade2)") (class "Default")
      (node (ref "J32") (pin "e2") (pinfunction "e2_e2") (pintype "bidirectional"))
      (node (ref "J32") (pin "f1") (pinfunction "f1_f1") (pintype "bidirectional"))
    )
    (net (code "79") (name "P3V3MP") (class "Default")
      (node (ref "C44") (pin "2") (pinfunction "2_2") (pintype "passive"))
      (node (ref "C45") (pin "2") (pinfunction "2_2") (pintype "passive"))
      (node (ref "J32") (pin "c2") (pinfunction "c2_c2") (pintype "bidirectional"))
      (node (ref "OSC1") (pin "1") (pinfunction "OE_1") (pintype "input"))
      (node (ref "OSC1") (pin "6") (pinfunction "VDD_6") (pintype "power_in"))
      (node (ref "OSC2") (pin "2") (pinfunction "OE_2") (pintype "input"))
      (node (ref "OSC2") (pin "6") (pinfunction "VDD_6") (pintype "power_in"))
    )
    (net (code "80") (name "P12V") (class "Default")
      (node (ref "J32") (pin "a1") (pinfunction "a1_a1") (pintype "bidirectional"))
      (node (ref "J32") (pin "a2") (pinfunction "a2_a2") (pintype "bidirectional"))
      (node (ref "J32") (pin "b1") (pinfunction "b1_b1") (pintype "bidirectional"))
      (node (ref "J32") (pin "b2") (pinfunction "b2_b2") (pintype "bidirectional"))
    )
    (net (code "81") (name "unconnected-(J32-Pada3)") (class "Default")
      (node (ref "J32") (pin "a3") (pinfunction "a3_a3") (pintype "bidirectional"))
    )
    (net (code "82") (name "unconnected-(J32-Pada4)") (class "Default")
      (node (ref "J32") (pin "a4") (pinfunction "a4_a4") (pintype "bidirectional"))
    )
    (net (code "83") (name "unconnected-(J32-Pada5)") (class "Default")
      (node (ref "J32") (pin "a5") (pinfunction "a5_a5") (pintype "bidirectional"))
    )
    (net (code "84") (name "unconnected-(J32-Pada6)") (class "Default")
      (node (ref "J32") (pin "a6") (pinfunction "a6_a6") (pintype "bidirectional"))
    )
    (net (code "85") (name "unconnected-(J32-Pada7)") (class "Default")
      (node (ref "J32") (pin "a7") (pinfunction "a7_a7") (pintype "bidirectional"))
    )
    (net (code "86") (name "unconnected-(J32-Pada8)") (class "Default")
      (node (ref "J32") (pin "a8") (pinfunction "a8_a8") (pintype "bidirectional"))
    )
    (net (code "87") (name "unconnected-(J32-Pada9)") (class "Default")
      (node (ref "J32") (pin "a9") (pinfunction "a9_a9") (pintype "bidirectional"))
    )
    (net (code "88") (name "unconnected-(J32-Pada10)") (class "Default")
      (node (ref "J32") (pin "a10") (pinfunction "a10_a10") (pintype "bidirectional"))
    )
    (net (code "89") (name "unconnected-(J32-Padb3)") (class "Default")
      (node (ref "J32") (pin "b3") (pinfunction "b3_b3") (pintype "bidirectional"))
    )
    (net (code "90") (name "unconnected-(J32-Padb4)") (class "Default")
      (node (ref "J32") (pin "b4") (pinfunction "b4_b4") (pintype "bidirectional"))
    )
    (net (code "91") (name "unconnected-(J32-Padb5)") (class "Default")
      (node (ref "J32") (pin "b5") (pinfunction "b5_b5") (pintype "bidirectional"))
    )
    (net (code "92") (name "unconnected-(J32-Padb6)") (class "Default")
      (node (ref "J32") (pin "b6") (pinfunction "b6_b6") (pintype "bidirectional"))
    )
    (net (code "93") (name "unconnected-(J32-Padb7)") (class "Default")
      (node (ref "J32") (pin "b7") (pinfunction "b7_b7") (pintype "bidirectional"))
    )
    (net (code "94") (name "unconnected-(J32-Padb8)") (class "Default")
      (node (ref "J32") (pin "b8") (pinfunction "b8_b8") (pintype "bidirectional"))
    )
    (net (code "95") (name "unconnected-(J32-Padb9)") (class "Default")
      (node (ref "J32") (pin "b9") (pinfunction "b9_b9") (pintype "bidirectional"))
    )
    (net (code "96") (name "unconnected-(J32-Padb10)") (class "Default")
      (node (ref "J32") (pin "b10") (pinfunction "b10_b10") (pintype "bidirectional"))
    )
    (net (code "97") (name "unconnected-(J32-Padc3)") (class "Default")
      (node (ref "J32") (pin "c3") (pinfunction "c3_c3") (pintype "bidirectional"))
    )
    (net (code "98") (name "unconnected-(J32-Padc4)") (class "Default")
      (node (ref "J32") (pin "c4") (pinfunction "c4_c4") (pintype "bidirectional"))
    )
    (net (code "99") (name "unconnected-(J32-Padd1)") (class "Default")
      (node (ref "J32") (pin "d1") (pinfunction "d1_d1") (pintype "bidirectional"))
    )
    (net (code "100") (name "unconnected-(J32-Padd2)") (class "Default")
      (node (ref "J32") (pin "d2") (pinfunction "d2_d2") (pintype "bidirectional"))
    )
    (net (code "101") (name "unconnected-(J32-Padd3)") (class "Default")
      (node (ref "J32") (pin "d3") (pinfunction "d3_d3") (pintype "bidirectional"))
    )
    (net (code "102") (name "unconnected-(J32-Padd4)") (class "Default")
      (node (ref "J32") (pin "d4") (pinfunction "d4_d4") (pintype "bidirectional"))
    )
    (net (code "103") (name "unconnected-(J32-Pade1)") (class "Default")
      (node (ref "J32") (pin "e1") (pinfunction "e1_e1") (pintype "bidirectional"))
    )
    (net (code "104") (name "unconnected-(J32-Pade3)") (class "Default")
      (node (ref "J32") (pin "e3") (pinfunction "e3_e3") (pintype "bidirectional"))
    )
    (net (code "105") (name "unconnected-(J32-Pade4)") (class "Default")
      (node (ref "J32") (pin "e4") (pinfunction "e4_e4") (pintype "bidirectional"))
    )
    (net (code "106") (name "unconnected-(J32-Padf2)") (class "Default")
      (node (ref "J32") (pin "f2") (pinfunction "f2_f2") (pintype "bidirectional"))
    )
    (net (code "107") (name "unconnected-(J32-Padf3)") (class "Default")
      (node (ref "J32") (pin "f3") (pinfunction "f3_f3") (pintype "bidirectional"))
    )
    (net (code "108") (name "unconnected-(J32-Padf4)") (class "Default")
      (node (ref "J32") (pin "f4") (pinfunction "f4_f4") (pintype "bidirectional"))
    )
    (net (code "109") (name "unconnected-(J34-Pada2)") (class "Default")
      (node (ref "J34") (pin "a2") (pinfunction "a2_a2") (pintype "bidirectional"))
    )
    (net (code "110") (name "unconnected-(J34-Pada3)") (class "Default")
      (node (ref "J34") (pin "a3") (pinfunction "a3_a3") (pintype "bidirectional"))
    )
    (net (code "111") (name "unconnected-(J34-Pada4)") (class "Default")
      (node (ref "J34") (pin "a4") (pinfunction "a4_a4") (pintype "bidirectional"))
    )
    (net (code "112") (name "unconnected-(J34-Pada6)") (class "Default")
      (node (ref "J34") (pin "a6") (pinfunction "a6_a6") (pintype "bidirectional"))
    )
    (net (code "113") (name "unconnected-(J34-Padb2)") (class "Default")
      (node (ref "J34") (pin "b2") (pinfunction "b2_b2") (pintype "bidirectional"))
    )
    (net (code "114") (name "unconnected-(J34-Padb3)") (class "Default")
      (node (ref "J34") (pin "b3") (pinfunction "b3_b3") (pintype "bidirectional"))
    )
    (net (code "115") (name "unconnected-(J34-Padb4)") (class "Default")
      (node (ref "J34") (pin "b4") (pinfunction "b4_b4") (pintype "bidirectional"))
    )
    (net (code "116") (name "unconnected-(J34-Padb6)") (class "Default")
      (node (ref "J34") (pin "b6") (pinfunction "b6_b6") (pintype "bidirectional"))
    )
    (net (code "117") (name "unconnected-(OSC1-NC-Pad2)") (class "Default")
      (node (ref "OSC1") (pin "2") (pinfunction "NC_2") (pintype "passive"))
    )
    (net (code "118") (name "unconnected-(OSC2-NC-Pad1)") (class "Default")
      (node (ref "OSC2") (pin "1") (pinfunction "NC_1") (pintype "passive"))
    )
  )
)
